# button32.net
KiCad netlist of a schematic drawn in EAGLE
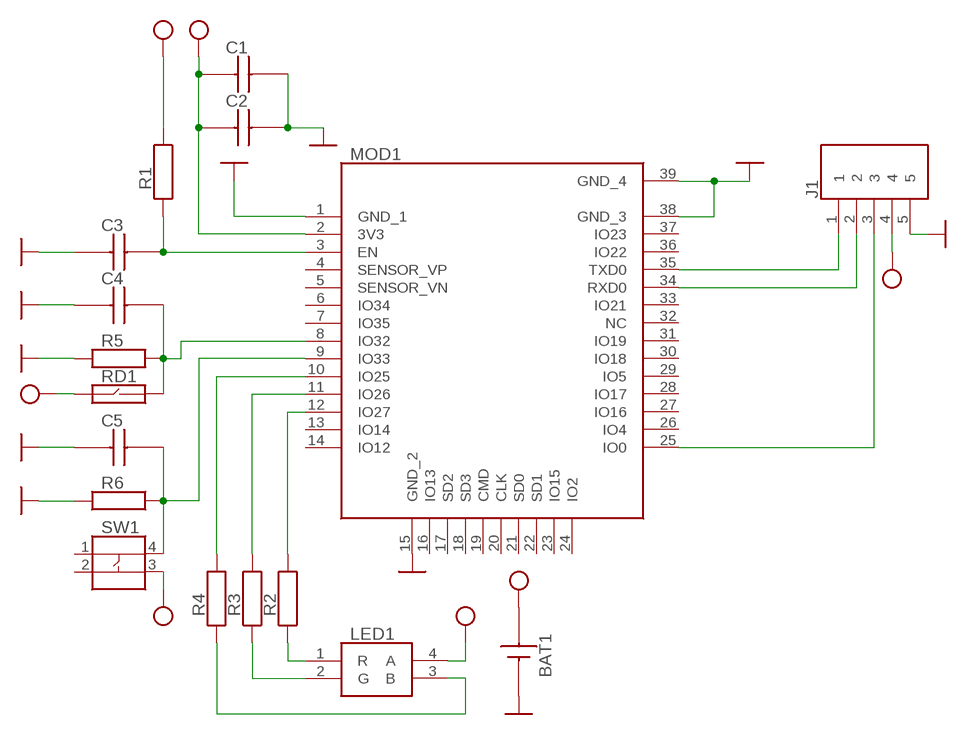
[diagram p0: schematic, sheet 1]

(export (version "E")
  (design (tool "Eeschema 10.0.6"))
  (components
    (comp (ref "BAT1")
      (value "BH-411-1P24")
      (footprint "eagle-import:BH-411-1P24")
      (libsource (lib "eagle-import") (part "BH-411-1P24"))
    )
    (comp (ref "C1")
      (value "CAPACITOR-0603")
      (footprint "eagle-import:0603")
      (libsource (lib "eagle-import") (part "CAPACITOR-0603"))
    )
    (comp (ref "C2")
      (value "CAPACITOR-0603")
      (footprint "eagle-import:0603")
      (libsource (lib "eagle-import") (part "CAPACITOR-0603"))
    )
    (comp (ref "C3")
      (value "CAPACITOR-0603")
      (footprint "eagle-import:0603")
      (libsource (lib "eagle-import") (part "CAPACITOR-0603"))
    )
    (comp (ref "C4")
      (value "CAPACITOR-0603")
      (footprint "eagle-import:0603")
      (libsource (lib "eagle-import") (part "CAPACITOR-0603"))
    )
    (comp (ref "C5")
      (value "CAPACITOR-0603")
      (footprint "eagle-import:0603")
      (libsource (lib "eagle-import") (part "CAPACITOR-0603"))
    )
    (comp (ref "J1")
      (value "HEADER-5P-DıP-2_54MM")
      (footprint "eagle-import:HEADER-5P-DıP-2_54MM")
      (libsource (lib "eagle-import") (part "HEADER-5P-DıP-2_54MM"))
    )
    (comp (ref "LED1")
      (value "LED-RGB-3528-PLCC4")
      (footprint "eagle-import:LED-RGB-3528-PLCC4")
      (libsource (lib "eagle-import") (part "LED-RGB-3528-PLCC4"))
    )
    (comp (ref "MOD1")
      (value "ESP32-WROOM-32D")
      (footprint "eagle-import:ESP32-WROOM-32D")
      (libsource (lib "eagle-import") (part "ESP32-WROOM-32D"))
    )
    (comp (ref "R1")
      (value "RESISTOR-0603")
      (footprint "eagle-import:0603")
      (libsource (lib "eagle-import") (part "RESISTOR-0603"))
    )
    (comp (ref "R2")
      (value "RESISTOR-0603")
      (footprint "eagle-import:0603")
      (libsource (lib "eagle-import") (part "RESISTOR-0603"))
    )
    (comp (ref "R3")
      (value "RESISTOR-0603")
      (footprint "eagle-import:0603")
      (libsource (lib "eagle-import") (part "RESISTOR-0603"))
    )
    (comp (ref "R4")
      (value "RESISTOR-0603")
      (footprint "eagle-import:0603")
      (libsource (lib "eagle-import") (part "RESISTOR-0603"))
    )
    (comp (ref "R5")
      (value "RESISTOR-0603")
      (footprint "eagle-import:0603")
      (libsource (lib "eagle-import") (part "RESISTOR-0603"))
    )
    (comp (ref "R6")
      (value "RESISTOR-0603")
      (footprint "eagle-import:0603")
      (libsource (lib "eagle-import") (part "RESISTOR-0603"))
    )
    (comp (ref "RD1")
      (value "REED")
      (footprint "eagle-import:0603")
      (libsource (lib "eagle-import") (part "REED"))
    )
    (comp (ref "SW1")
      (value "BUTTON-4P-SMD-5X5")
      (footprint "eagle-import:BUTTON-4P-SMD-5X5")
      (libsource (lib "eagle-import") (part "BUTTON-4P-SMD-5X5"))
    )
  )
  (nets
    (net (code "1") (name "GND") (class "Default")
      (node (ref "BAT1") (pin "2") (pinfunction "-_2") (pintype "power_in"))
      (node (ref "C1") (pin "2") (pinfunction "2_2") (pintype "passive"))
      (node (ref "C2") (pin "2") (pinfunction "2_2") (pintype "passive"))
      (node (ref "C3") (pin "1") (pinfunction "1_1") (pintype "passive"))
      (node (ref "C4") (pin "1") (pinfunction "1_1") (pintype "passive"))
      (node (ref "C5") (pin "1") (pinfunction "1_1") (pintype "passive"))
      (node (ref "J1") (pin "5") (pinfunction "5_5") (pintype "bidirectional"))
      (node (ref "MOD1") (pin "1") (pinfunction "GND_1_1") (pintype "power_in"))
      (node (ref "MOD1") (pin "15") (pinfunction "GND_2_15") (pintype "power_in"))
      (node (ref "MOD1") (pin "38") (pinfunction "GND_3_38") (pintype "power_in"))
      (node (ref "MOD1") (pin "39") (pinfunction "GND_4_39") (pintype "power_in"))
      (node (ref "R5") (pin "1") (pinfunction "1_1") (pintype "passive"))
      (node (ref "R6") (pin "1") (pinfunction "1_1") (pintype "passive"))
    )
    (net (code "2") (name "Net-(LED1-B)") (class "Default")
      (node (ref "LED1") (pin "3") (pinfunction "B_3") (pintype "bidirectional"))
      (node (ref "R4") (pin "1") (pinfunction "1_1") (pintype "passive"))
    )
    (net (code "3") (name "Net-(LED1-G)") (class "Default")
      (node (ref "LED1") (pin "2") (pinfunction "G_2") (pintype "bidirectional"))
      (node (ref "R3") (pin "1") (pinfunction "1_1") (pintype "passive"))
    )
    (net (code "4") (name "Net-(LED1-R)") (class "Default")
      (node (ref "LED1") (pin "1") (pinfunction "R_1") (pintype "bidirectional"))
      (node (ref "R2") (pin "1") (pinfunction "1_1") (pintype "passive"))
    )
    (net (code "5") (name "Net-(MOD1-EN)") (class "Default")
      (node (ref "C3") (pin "2") (pinfunction "2_2") (pintype "passive"))
      (node (ref "MOD1") (pin "3") (pinfunction "EN_3") (pintype "bidirectional"))
      (node (ref "R1") (pin "1") (pinfunction "1_1") (pintype "passive"))
    )
    (net (code "6") (name "Net-(MOD1-IO0)") (class "Default")
      (node (ref "J1") (pin "3") (pinfunction "3_3") (pintype "bidirectional"))
      (node (ref "MOD1") (pin "25") (pinfunction "IO0_25") (pintype "bidirectional"))
    )
    (net (code "7") (name "Net-(MOD1-IO25)") (class "Default")
      (node (ref "MOD1") (pin "10") (pinfunction "IO25_10") (pintype "bidirectional"))
      (node (ref "R4") (pin "2") (pinfunction "2_2") (pintype "passive"))
    )
    (net (code "8") (name "Net-(MOD1-IO26)") (class "Default")
      (node (ref "MOD1") (pin "11") (pinfunction "IO26_11") (pintype "bidirectional"))
      (node (ref "R3") (pin "2") (pinfunction "2_2") (pintype "passive"))
    )
    (net (code "9") (name "Net-(MOD1-IO27)") (class "Default")
      (node (ref "MOD1") (pin "12") (pinfunction "IO27_12") (pintype "bidirectional"))
      (node (ref "R2") (pin "2") (pinfunction "2_2") (pintype "passive"))
    )
    (net (code "10") (name "Net-(MOD1-IO32)") (class "Default")
      (node (ref "C4") (pin "2") (pinfunction "2_2") (pintype "passive"))
      (node (ref "MOD1") (pin "8") (pinfunction "IO32_8") (pintype "bidirectional"))
      (node (ref "R5") (pin "2") (pinfunction "2_2") (pintype "passive"))
      (node (ref "RD1") (pin "2") (pinfunction "2_2") (pintype "passive"))
    )
    (net (code "11") (name "Net-(MOD1-IO33)") (class "Default")
      (node (ref "C5") (pin "2") (pinfunction "2_2") (pintype "passive"))
      (node (ref "MOD1") (pin "9") (pinfunction "IO33_9") (pintype "bidirectional"))
      (node (ref "R6") (pin "2") (pinfunction "2_2") (pintype "passive"))
      (node (ref "SW1") (pin "4") (pinfunction "4_4") (pintype "passive"))
    )
    (net (code "12") (name "Net-(MOD1-RXD0)") (class "Default")
      (node (ref "J1") (pin "2") (pinfunction "2_2") (pintype "bidirectional"))
      (node (ref "MOD1") (pin "34") (pinfunction "RXD0_34") (pintype "bidirectional"))
    )
    (net (code "13") (name "Net-(MOD1-TXD0)") (class "Default")
      (node (ref "J1") (pin "1") (pinfunction "1_1") (pintype "bidirectional"))
      (node (ref "MOD1") (pin "35") (pinfunction "TXD0_35") (pintype "bidirectional"))
    )
    (net (code "14") (name "VCC") (class "Default")
      (node (ref "BAT1") (pin "1") (pinfunction "+_1") (pintype "power_in"))
      (node (ref "C1") (pin "1") (pinfunction "1_1") (pintype "passive"))
      (node (ref "C2") (pin "1") (pinfunction "1_1") (pintype "passive"))
      (node (ref "J1") (pin "4") (pinfunction "4_4") (pintype "bidirectional"))
      (node (ref "LED1") (pin "4") (pinfunction "A_4") (pintype "bidirectional"))
      (node (ref "MOD1") (pin "2") (pinfunction "3V3_2") (pintype "power_in"))
      (node (ref "R1") (pin "2") (pinfunction "2_2") (pintype "passive"))
      (node (ref "RD1") (pin "1") (pinfunction "1_1") (pintype "passive"))
      (node (ref "SW1") (pin "3") (pinfunction "3_3") (pintype "passive"))
    )
    (net (code "15") (name "unconnected-(MOD1-CLK-Pad20)") (class "Default")
      (node (ref "MOD1") (pin "20") (pinfunction "CLK_20") (pintype "bidirectional"))
    )
    (net (code "16") (name "unconnected-(MOD1-CMD-Pad19)") (class "Default")
      (node (ref "MOD1") (pin "19") (pinfunction "CMD_19") (pintype "bidirectional"))
    )
    (net (code "17") (name "unconnected-(MOD1-IO2-Pad24)") (class "Default")
      (node (ref "MOD1") (pin "24") (pinfunction "IO2_24") (pintype "bidirectional"))
    )
    (net (code "18") (name "unconnected-(MOD1-IO4-Pad26)") (class "Default")
      (node (ref "MOD1") (pin "26") (pinfunction "IO4_26") (pintype "bidirectional"))
    )
    (net (code "19") (name "unconnected-(MOD1-IO5-Pad29)") (class "Default")
      (node (ref "MOD1") (pin "29") (pinfunction "IO5_29") (pintype "bidirectional"))
    )
    (net (code "20") (name "unconnected-(MOD1-IO12-Pad14)") (class "Default")
      (node (ref "MOD1") (pin "14") (pinfunction "IO12_14") (pintype "bidirectional"))
    )
    (net (code "21") (name "unconnected-(MOD1-IO13-Pad16)") (class "Default")
      (node (ref "MOD1") (pin "16") (pinfunction "IO13_16") (pintype "bidirectional"))
    )
    (net (code "22") (name "unconnected-(MOD1-IO14-Pad13)") (class "Default")
      (node (ref "MOD1") (pin "13") (pinfunction "IO14_13") (pintype "bidirectional"))
    )
    (net (code "23") (name "unconnected-(MOD1-IO15-Pad23)") (class "Default")
      (node (ref "MOD1") (pin "23") (pinfunction "IO15_23") (pintype "bidirectional"))
    )
    (net (code "24") (name "unconnected-(MOD1-IO16-Pad27)") (class "Default")
      (node (ref "MOD1") (pin "27") (pinfunction "IO16_27") (pintype "bidirectional"))
    )
    (net (code "25") (name "unconnected-(MOD1-IO17-Pad28)") (class "Default")
      (node (ref "MOD1") (pin "28") (pinfunction "IO17_28") (pintype "bidirectional"))
    )
    (net (code "26") (name "unconnected-(MOD1-IO18-Pad30)") (class "Default")
      (node (ref "MOD1") (pin "30") (pinfunction "IO18_30") (pintype "bidirectional"))
    )
    (net (code "27") (name "unconnected-(MOD1-IO19-Pad31)") (class "Default")
      (node (ref "MOD1") (pin "31") (pinfunction "IO19_31") (pintype "bidirectional"))
    )
    (net (code "28") (name "unconnected-(MOD1-IO21-Pad33)") (class "Default")
      (node (ref "MOD1") (pin "33") (pinfunction "IO21_33") (pintype "bidirectional"))
    )
    (net (code "29") (name "unconnected-(MOD1-IO22-Pad36)") (class "Default")
      (node (ref "MOD1") (pin "36") (pinfunction "IO22_36") (pintype "bidirectional"))
    )
    (net (code "30") (name "unconnected-(MOD1-IO23-Pad37)") (class "Default")
      (node (ref "MOD1") (pin "37") (pinfunction "IO23_37") (pintype "bidirectional"))
    )
    (net (code "31") (name "unconnected-(MOD1-IO34-Pad6)") (class "Default")
      (node (ref "MOD1") (pin "6") (pinfunction "IO34_6") (pintype "bidirectional"))
    )
    (net (code "32") (name "unconnected-(MOD1-IO35-Pad7)") (class "Default")
      (node (ref "MOD1") (pin "7") (pinfunction "IO35_7") (pintype "bidirectional"))
    )
    (net (code "33") (name "unconnected-(MOD1-NC-Pad32)") (class "Default")
      (node (ref "MOD1") (pin "32") (pinfunction "NC_32") (pintype "no_connect"))
    )
    (net (code "34") (name "unconnected-(MOD1-SD0-Pad21)") (class "Default")
      (node (ref "MOD1") (pin "21") (pinfunction "SD0_21") (pintype "bidirectional"))
    )
    (net (code "35") (name "unconnected-(MOD1-SD1-Pad22)") (class "Default")
      (node (ref "MOD1") (pin "22") (pinfunction "SD1_22") (pintype "bidirectional"))
    )
    (net (code "36") (name "unconnected-(MOD1-SD2-Pad17)") (class "Default")
      (node (ref "MOD1") (pin "17") (pinfunction "SD2_17") (pintype "bidirectional"))
    )
    (net (code "37") (name "unconnected-(MOD1-SD3-Pad18)") (class "Default")
      (node (ref "MOD1") (pin "18") (pinfunction "SD3_18") (pintype "bidirectional"))
    )
    (net (code "38") (name "unconnected-(MOD1-SENSOR_VN-Pad5)") (class "Default")
      (node (ref "MOD1") (pin "5") (pinfunction "SENSOR_VN_5") (pintype "bidirectional"))
    )
    (net (code "39") (name "unconnected-(MOD1-SENSOR_VP-Pad4)") (class "Default")
      (node (ref "MOD1") (pin "4") (pinfunction "SENSOR_VP_4") (pintype "bidirectional"))
    )
    (net (code "40") (name "unconnected-(SW1-Pad1)") (class "Default")
      (node (ref "SW1") (pin "1") (pinfunction "1_1") (pintype "passive"))
    )
    (net (code "41") (name "unconnected-(SW1-Pad2)") (class "Default")
      (node (ref "SW1") (pin "2") (pinfunction "2_2") (pintype "passive"))
    )
  )
)
